# main.net
KiCad netlist of a schematic drawn in Altium Designer
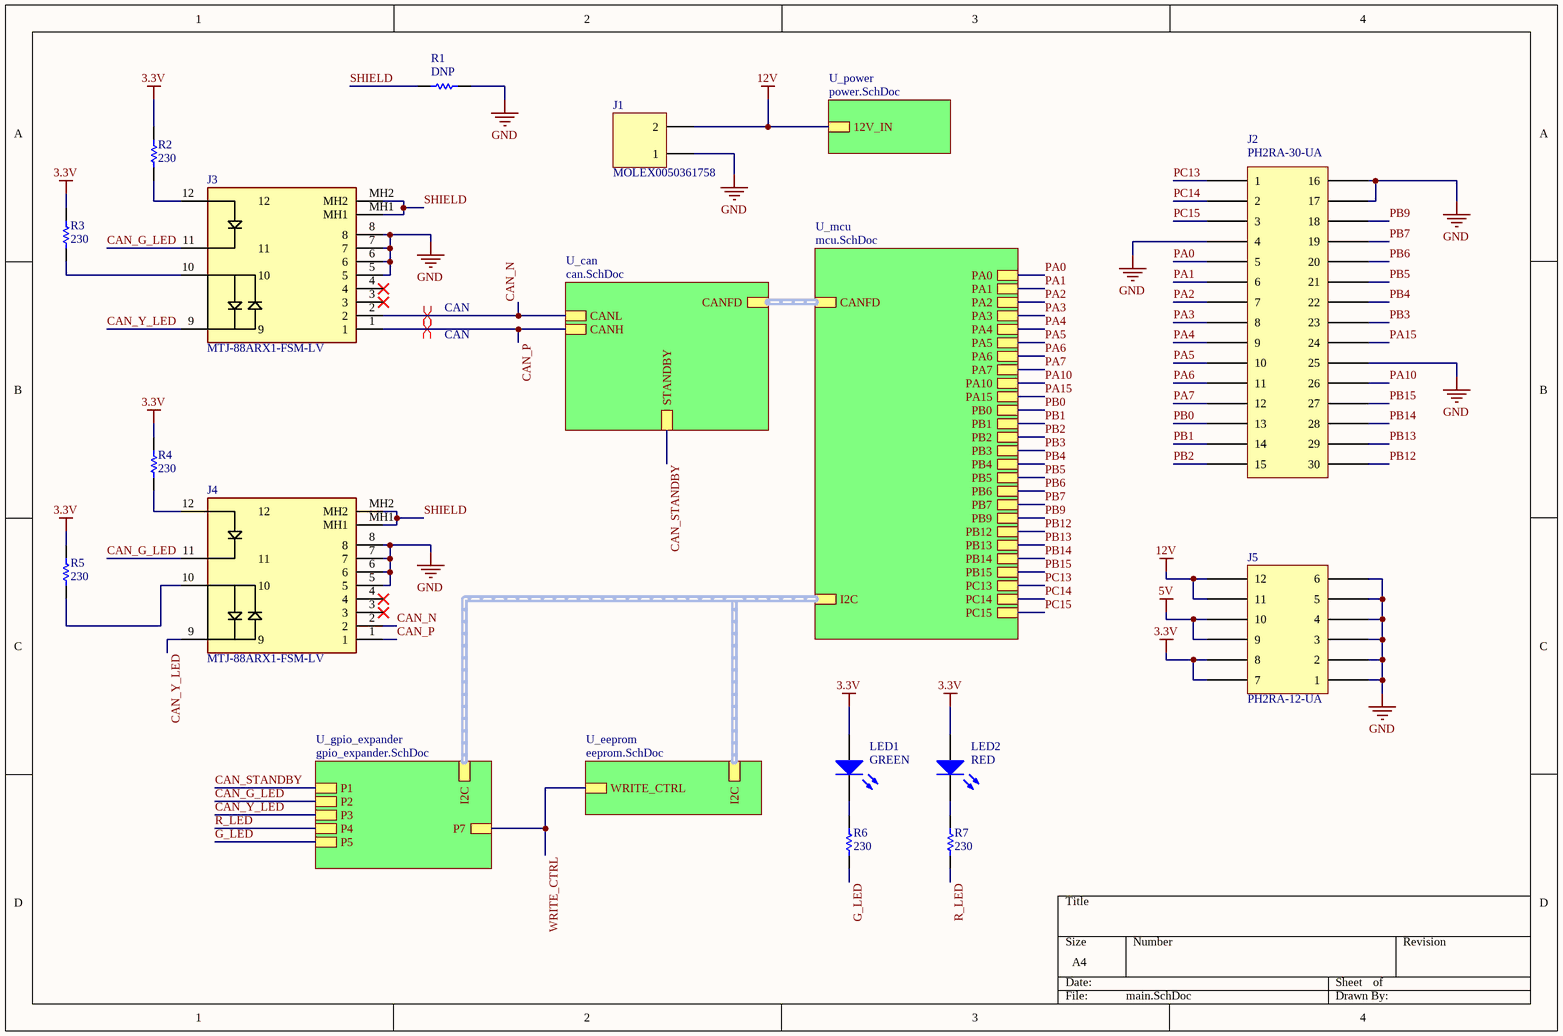
[diagram p0: main.SchDoc]

(export (version "E")
  (design (tool "Eeschema 10.0.6"))
  (components
    (comp (ref "J1")
      (value "MOLEX0050361758")
      (footprint "Molex0050361758")
      (description "Connector Header Through Hole, Right Angle 2 position -")
      (fields (field (name "MANUFACTURER") "Molex") (field (name "MANUFACTURER PART NUMBER") "0050361758"))
      (libsource (lib "GeneralConnectors") (part "MOLEX0050361758"))
    )
    (comp (ref "J2")
      (value "PH2RA-30-UA")
      (footprint "PH2RA-30-UA")
      (description "Connector Header Through Hole, Right Angle 30 position 0.100\" (2.54mm)")
      (fields (field (name "MANUFACTURER") "Adam Tech"))
      (libsource (lib "GeneralConnectors") (part "PH2RA-30-UA"))
    )
    (comp (ref "J3")
      (value "MTJ-88ARX1-FSM-LV")
      (footprint "MTJ-88ARX1-FSM-LV")
      (description "RJ45 Connector")
      (libsource (lib "GeneralConnectors") (part "MTJ-88ARX1-FSM-LV"))
    )
    (comp (ref "J4")
      (value "MTJ-88ARX1-FSM-LV")
      (footprint "MTJ-88ARX1-FSM-LV")
      (description "RJ45 Connector")
      (libsource (lib "GeneralConnectors") (part "MTJ-88ARX1-FSM-LV"))
    )
    (comp (ref "J5")
      (value "PH2RA-12-UA")
      (footprint "PH2RA-12-UA")
      (description "Connector Header Through Hole, Right Angle 12 position 0.100\" (2.54mm)")
      (fields
        (field (name "MANUFACTURER") "Adam Tech")
        (field (name "MANUFACTURER PART NUMBER") "PH2RA-30-UA")
      )
      (libsource (lib "GeneralConnectors") (part "PH2RA-12-UA"))
    )
    (comp (ref "LED1")
      (value "GREEN")
      (footprint "0805 - DIODE")
      (description "Light Emitting Diode")
      (libsource (lib "General") (part "LED"))
    )
    (comp (ref "LED2")
      (value "RED")
      (footprint "0805 - DIODE")
      (description "Light Emitting Diode")
      (libsource (lib "General") (part "LED"))
    )
    (comp (ref "R1")
      (value "DNP")
      (footprint "0603 - Resistor")
      (description "Resistor")
      (libsource (lib "General") (part "Resistor"))
    )
    (comp (ref "R2")
      (value "230")
      (footprint "0603 - Resistor")
      (description "Resistor")
      (libsource (lib "General") (part "Resistor"))
    )
    (comp (ref "R3")
      (value "230")
      (footprint "0603 - Resistor")
      (description "Resistor")
      (libsource (lib "General") (part "Resistor"))
    )
    (comp (ref "R4")
      (value "230")
      (footprint "0603 - Resistor")
      (description "Resistor")
      (libsource (lib "General") (part "Resistor"))
    )
    (comp (ref "R5")
      (value "230")
      (footprint "0603 - Resistor")
      (description "Resistor")
      (libsource (lib "General") (part "Resistor"))
    )
    (comp (ref "R6")
      (value "230")
      (footprint "0603 - Resistor")
      (description "Resistor")
      (libsource (lib "General") (part "Resistor"))
    )
    (comp (ref "R7")
      (value "230")
      (footprint "0603 - Resistor")
      (description "Resistor")
      (libsource (lib "General") (part "Resistor"))
    )
  )
  (nets
    (net (code "2") (name "/CAN_G_LED") (class "Default")
      (node (ref "J3") (pin "11") (pinfunction "11_11") (pintype "passive"))
      (node (ref "J4") (pin "11") (pinfunction "11_11") (pintype "passive"))
    )
    (net (code "3") (name "/CAN_N") (class "Default")
      (node (ref "J3") (pin "2") (pinfunction "2_2") (pintype "passive"))
      (node (ref "J4") (pin "2") (pinfunction "2_2") (pintype "passive"))
    )
    (net (code "4") (name "/CAN_P") (class "Default")
      (node (ref "J3") (pin "1") (pinfunction "1_1") (pintype "passive"))
      (node (ref "J4") (pin "1") (pinfunction "1_1") (pintype "passive"))
    )
    (net (code "6") (name "/CAN_Y_LED") (class "Default")
      (node (ref "J3") (pin "9") (pinfunction "9_9") (pintype "passive"))
      (node (ref "J4") (pin "9") (pinfunction "9_9") (pintype "passive"))
    )
    (net (code "7") (name "/G_LED") (class "Default")
      (node (ref "R6") (pin "2") (pinfunction "2_2") (pintype "passive"))
    )
    (net (code "9") (name "/PA0") (class "Default")
      (node (ref "J2") (pin "5") (pinfunction "5_5") (pintype "passive"))
    )
    (net (code "10") (name "/PA1") (class "Default")
      (node (ref "J2") (pin "6") (pinfunction "6_6") (pintype "passive"))
    )
    (net (code "11") (name "/PA2") (class "Default")
      (node (ref "J2") (pin "7") (pinfunction "7_7") (pintype "passive"))
    )
    (net (code "12") (name "/PA3") (class "Default")
      (node (ref "J2") (pin "8") (pinfunction "8_8") (pintype "passive"))
    )
    (net (code "13") (name "/PA4") (class "Default")
      (node (ref "J2") (pin "9") (pinfunction "9_9") (pintype "passive"))
    )
    (net (code "14") (name "/PA5") (class "Default")
      (node (ref "J2") (pin "10") (pinfunction "10_10") (pintype "passive"))
    )
    (net (code "15") (name "/PA6") (class "Default")
      (node (ref "J2") (pin "11") (pinfunction "11_11") (pintype "passive"))
    )
    (net (code "16") (name "/PA7") (class "Default")
      (node (ref "J2") (pin "12") (pinfunction "12_12") (pintype "passive"))
    )
    (net (code "17") (name "/PA10") (class "Default")
      (node (ref "J2") (pin "26") (pinfunction "26_26") (pintype "passive"))
    )
    (net (code "18") (name "/PA15") (class "Default")
      (node (ref "J2") (pin "24") (pinfunction "24_24") (pintype "passive"))
    )
    (net (code "19") (name "/PB0") (class "Default")
      (node (ref "J2") (pin "13") (pinfunction "13_13") (pintype "passive"))
    )
    (net (code "20") (name "/PB1") (class "Default")
      (node (ref "J2") (pin "14") (pinfunction "14_14") (pintype "passive"))
    )
    (net (code "21") (name "/PB2") (class "Default")
      (node (ref "J2") (pin "15") (pinfunction "15_15") (pintype "passive"))
    )
    (net (code "22") (name "/PB3") (class "Default")
      (node (ref "J2") (pin "23") (pinfunction "23_23") (pintype "passive"))
    )
    (net (code "23") (name "/PB4") (class "Default")
      (node (ref "J2") (pin "22") (pinfunction "22_22") (pintype "passive"))
    )
    (net (code "24") (name "/PB5") (class "Default")
      (node (ref "J2") (pin "21") (pinfunction "21_21") (pintype "passive"))
    )
    (net (code "25") (name "/PB6") (class "Default")
      (node (ref "J2") (pin "20") (pinfunction "20_20") (pintype "passive"))
    )
    (net (code "26") (name "/PB7") (class "Default")
      (node (ref "J2") (pin "19") (pinfunction "19_19") (pintype "passive"))
    )
    (net (code "27") (name "/PB9") (class "Default")
      (node (ref "J2") (pin "18") (pinfunction "18_18") (pintype "passive"))
    )
    (net (code "28") (name "/PB12") (class "Default")
      (node (ref "J2") (pin "30") (pinfunction "30_30") (pintype "passive"))
    )
    (net (code "29") (name "/PB13") (class "Default")
      (node (ref "J2") (pin "29") (pinfunction "29_29") (pintype "passive"))
    )
    (net (code "30") (name "/PB14") (class "Default")
      (node (ref "J2") (pin "28") (pinfunction "28_28") (pintype "passive"))
    )
    (net (code "31") (name "/PB15") (class "Default")
      (node (ref "J2") (pin "27") (pinfunction "27_27") (pintype "passive"))
    )
    (net (code "32") (name "/PC13") (class "Default")
      (node (ref "J2") (pin "1") (pinfunction "1_1") (pintype "passive"))
    )
    (net (code "33") (name "/PC14") (class "Default")
      (node (ref "J2") (pin "2") (pinfunction "2_2") (pintype "passive"))
    )
    (net (code "34") (name "/PC15") (class "Default")
      (node (ref "J2") (pin "3") (pinfunction "3_3") (pintype "passive"))
    )
    (net (code "35") (name "/R_LED") (class "Default")
      (node (ref "R7") (pin "2") (pinfunction "2_2") (pintype "passive"))
    )
    (net (code "36") (name "/SHIELD") (class "Default")
      (node (ref "J3") (pin "MH1") (pinfunction "MH1_MH1") (pintype "passive"))
      (node (ref "J3") (pin "MH2") (pinfunction "MH2_MH2") (pintype "passive"))
      (node (ref "J4") (pin "MH1") (pinfunction "MH1_MH1") (pintype "passive"))
      (node (ref "J4") (pin "MH2") (pinfunction "MH2_MH2") (pintype "passive"))
      (node (ref "R1") (pin "2") (pinfunction "2_2") (pintype "passive"))
    )
    (net (code "38") (name "3.3V") (class "Default")
      (node (ref "J5") (pin "7") (pinfunction "7_7") (pintype "passive"))
      (node (ref "J5") (pin "8") (pinfunction "8_8") (pintype "passive"))
      (node (ref "LED1") (pin "1") (pinfunction "A_1") (pintype "passive"))
      (node (ref "LED2") (pin "1") (pinfunction "A_1") (pintype "passive"))
      (node (ref "R2") (pin "1") (pinfunction "1_1") (pintype "passive"))
      (node (ref "R3") (pin "1") (pinfunction "1_1") (pintype "passive"))
      (node (ref "R4") (pin "1") (pinfunction "1_1") (pintype "passive"))
      (node (ref "R5") (pin "1") (pinfunction "1_1") (pintype "passive"))
    )
    (net (code "39") (name "5V") (class "Default")
      (node (ref "J5") (pin "10") (pinfunction "10_10") (pintype "passive"))
      (node (ref "J5") (pin "9") (pinfunction "9_9") (pintype "passive"))
    )
    (net (code "40") (name "12V") (class "Default")
      (node (ref "J1") (pin "2") (pinfunction "2_2") (pintype "passive"))
      (node (ref "J5") (pin "11") (pinfunction "11_11") (pintype "passive"))
      (node (ref "J5") (pin "12") (pinfunction "12_12") (pintype "passive"))
    )
    (net (code "41") (name "GND") (class "Default")
      (node (ref "J1") (pin "1") (pinfunction "1_1") (pintype "passive"))
      (node (ref "J2") (pin "16") (pinfunction "16_16") (pintype "passive"))
      (node (ref "J2") (pin "17") (pinfunction "17_17") (pintype "passive"))
      (node (ref "J2") (pin "25") (pinfunction "25_25") (pintype "passive"))
      (node (ref "J2") (pin "4") (pinfunction "4_4") (pintype "passive"))
      (node (ref "J3") (pin "5") (pinfunction "5_5") (pintype "passive"))
      (node (ref "J3") (pin "6") (pinfunction "6_6") (pintype "passive"))
      (node (ref "J3") (pin "7") (pinfunction "7_7") (pintype "passive"))
      (node (ref "J3") (pin "8") (pinfunction "8_8") (pintype "passive"))
      (node (ref "J4") (pin "5") (pinfunction "5_5") (pintype "passive"))
      (node (ref "J4") (pin "6") (pinfunction "6_6") (pintype "passive"))
      (node (ref "J4") (pin "7") (pinfunction "7_7") (pintype "passive"))
      (node (ref "J4") (pin "8") (pinfunction "8_8") (pintype "passive"))
      (node (ref "J5") (pin "1") (pinfunction "1_1") (pintype "passive"))
      (node (ref "J5") (pin "2") (pinfunction "2_2") (pintype "passive"))
      (node (ref "J5") (pin "3") (pinfunction "3_3") (pintype "passive"))
      (node (ref "J5") (pin "4") (pinfunction "4_4") (pintype "passive"))
      (node (ref "J5") (pin "5") (pinfunction "5_5") (pintype "passive"))
      (node (ref "J5") (pin "6") (pinfunction "6_6") (pintype "passive"))
      (node (ref "R1") (pin "1") (pinfunction "1_1") (pintype "passive"))
    )
    (net (code "42") (name "Net-(J3-Pad10)") (class "Default")
      (node (ref "J3") (pin "10") (pinfunction "10_10") (pintype "passive"))
      (node (ref "R3") (pin "2") (pinfunction "2_2") (pintype "passive"))
    )
    (net (code "43") (name "Net-(J3-Pad12)") (class "Default")
      (node (ref "J3") (pin "12") (pinfunction "12_12") (pintype "passive"))
      (node (ref "R2") (pin "2") (pinfunction "2_2") (pintype "passive"))
    )
    (net (code "44") (name "Net-(J4-Pad10)") (class "Default")
      (node (ref "J4") (pin "10") (pinfunction "10_10") (pintype "passive"))
      (node (ref "R5") (pin "2") (pinfunction "2_2") (pintype "passive"))
    )
    (net (code "45") (name "Net-(J4-Pad12)") (class "Default")
      (node (ref "J4") (pin "12") (pinfunction "12_12") (pintype "passive"))
      (node (ref "R4") (pin "2") (pinfunction "2_2") (pintype "passive"))
    )
    (net (code "46") (name "Net-(LED1-K)") (class "Default")
      (node (ref "LED1") (pin "2") (pinfunction "K_2") (pintype "passive"))
      (node (ref "R6") (pin "1") (pinfunction "1_1") (pintype "passive"))
    )
    (net (code "47") (name "Net-(LED2-K)") (class "Default")
      (node (ref "LED2") (pin "2") (pinfunction "K_2") (pintype "passive"))
      (node (ref "R7") (pin "1") (pinfunction "1_1") (pintype "passive"))
    )
    (net (code "48") (name "unconnected-(J3-Pad3)") (class "Default")
      (node (ref "J3") (pin "3") (pinfunction "3_3") (pintype "passive+no_connect"))
    )
    (net (code "49") (name "unconnected-(J3-Pad4)") (class "Default")
      (node (ref "J3") (pin "4") (pinfunction "4_4") (pintype "passive+no_connect"))
    )
    (net (code "50") (name "unconnected-(J4-Pad3)") (class "Default")
      (node (ref "J4") (pin "3") (pinfunction "3_3") (pintype "passive+no_connect"))
    )
    (net (code "51") (name "unconnected-(J4-Pad4)") (class "Default")
      (node (ref "J4") (pin "4") (pinfunction "4_4") (pintype "passive+no_connect"))
    )
  )
)
